# SW3S.net
KiCad netlist of a schematic drawn in EAGLE
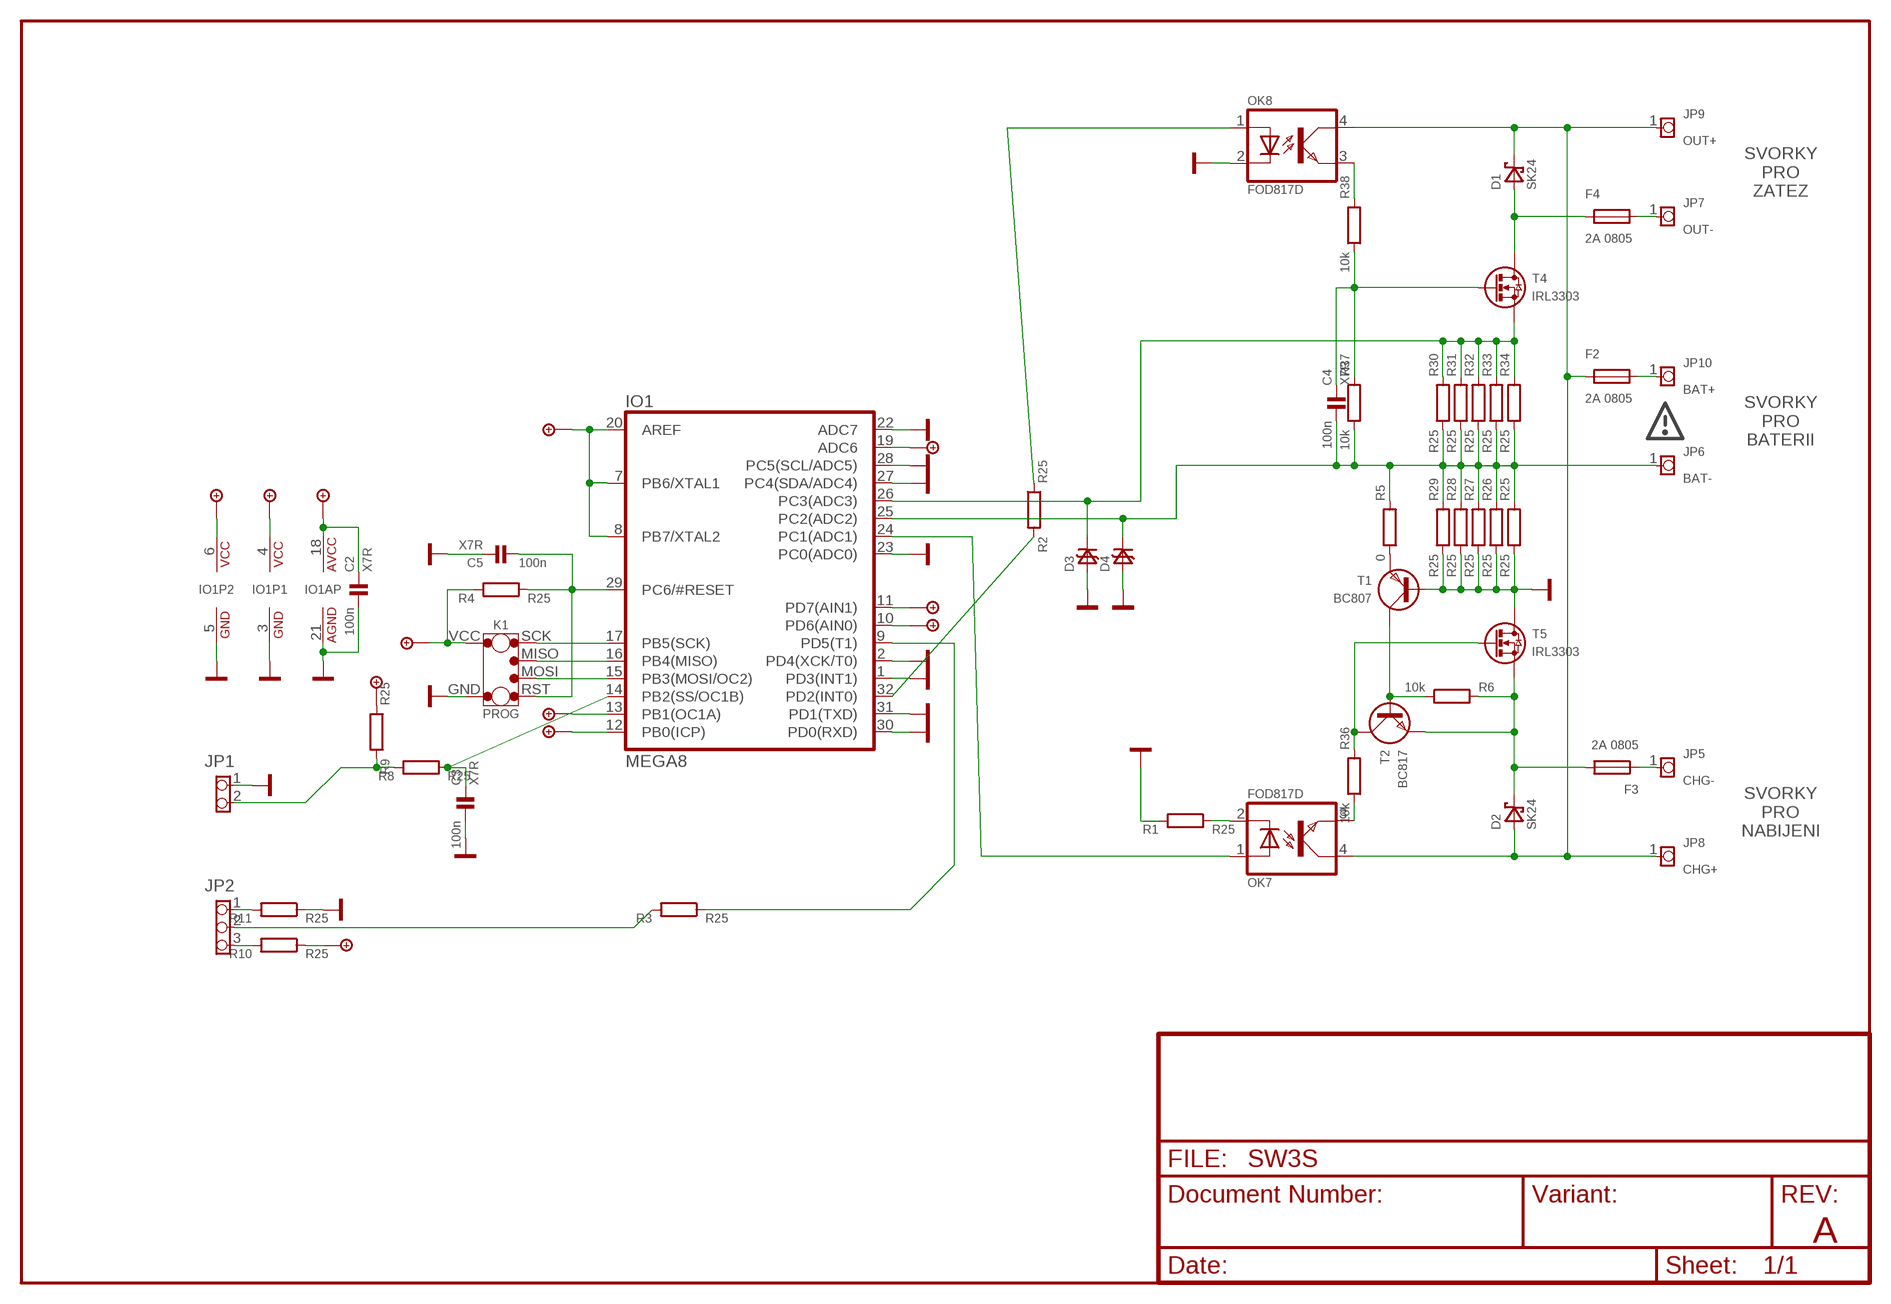
[diagram p0: schematic, sheet 1]

(export (version "E")
  (design (tool "Eeschema 10.0.6"))
  (components
    (comp (ref "C2")
      (value "100n")
      (footprint "eagle-import:0805")
      (libsource (lib "eagle-import") (part "C0805"))
    )
    (comp (ref "C3")
      (value "100n")
      (footprint "eagle-import:0805")
      (libsource (lib "eagle-import") (part "C0805"))
    )
    (comp (ref "C4")
      (value "100n")
      (footprint "eagle-import:0805")
      (libsource (lib "eagle-import") (part "C0805"))
    )
    (comp (ref "C5")
      (value "100n")
      (footprint "eagle-import:0805")
      (libsource (lib "eagle-import") (part "C0805"))
    )
    (comp (ref "D1")
      (value "SK24")
      (footprint "eagle-import:D_SMB")
      (libsource (lib "eagle-import") (part "D_SCHOTKY_SMB"))
    )
    (comp (ref "D2")
      (value "SK24")
      (footprint "eagle-import:D_SMB")
      (libsource (lib "eagle-import") (part "D_SCHOTKY_SMB"))
    )
    (comp (ref "D3")
      (value "D_TRANSIL_MLL34")
      (footprint "eagle-import:D_MLL34")
      (libsource (lib "eagle-import") (part "D_TRANSIL_MLL34"))
    )
    (comp (ref "D4")
      (value "D_TRANSIL_MLL34")
      (footprint "eagle-import:D_MLL34")
      (libsource (lib "eagle-import") (part "D_TRANSIL_MLL34"))
    )
    (comp (ref "F2")
      (value "2A 0805")
      (footprint "eagle-import:0805")
      (libsource (lib "eagle-import") (part "F_0805"))
    )
    (comp (ref "F3")
      (value "2A 0805")
      (footprint "eagle-import:0805")
      (libsource (lib "eagle-import") (part "F_0805"))
    )
    (comp (ref "F4")
      (value "2A 0805")
      (footprint "eagle-import:0805")
      (libsource (lib "eagle-import") (part "F_0805"))
    )
    (comp (ref "IO1")
      (value "MEGA8")
      (footprint "eagle-import:TQFP32")
      (libsource (lib "eagle-import") (part "MEGA8"))
    )
    (comp (ref "JP1")
      (value "PINHD-1X2_254_EDGE")
      (footprint "eagle-import:1X02_254_EDGE")
      (libsource (lib "eagle-import") (part "PINHD-1X2_254_EDGE"))
    )
    (comp (ref "JP2")
      (value "PINHD-1X3_254_EDGE")
      (footprint "eagle-import:1X03_254_EDGE")
      (libsource (lib "eagle-import") (part "PINHD-1X3_254_EDGE"))
    )
    (comp (ref "JP5")
      (value "CHG-")
      (footprint "eagle-import:1X01_254_PAD")
      (libsource (lib "eagle-import") (part "PINHD-1X1_254_PAD"))
    )
    (comp (ref "JP6")
      (value "BAT-")
      (footprint "eagle-import:1X01_254_PAD")
      (libsource (lib "eagle-import") (part "PINHD-1X1_254_PAD"))
    )
    (comp (ref "JP7")
      (value "OUT-")
      (footprint "eagle-import:1X01_254_PAD")
      (libsource (lib "eagle-import") (part "PINHD-1X1_254_PAD"))
    )
    (comp (ref "JP8")
      (value "CHG+")
      (footprint "eagle-import:1X01_254_PAD")
      (libsource (lib "eagle-import") (part "PINHD-1X1_254_PAD"))
    )
    (comp (ref "JP9")
      (value "OUT+")
      (footprint "eagle-import:1X01_254_PAD")
      (libsource (lib "eagle-import") (part "PINHD-1X1_254_PAD"))
    )
    (comp (ref "JP10")
      (value "BAT+")
      (footprint "eagle-import:1X01_254_PAD")
      (libsource (lib "eagle-import") (part "PINHD-1X1_254_PAD"))
    )
    (comp (ref "K1")
      (value "PROG")
      (footprint "eagle-import:PROG")
      (libsource (lib "eagle-import") (part "PROG"))
    )
    (comp (ref "OK7")
      (value "FOD817D")
      (footprint "eagle-import:SO04")
      (libsource (lib "eagle-import") (part "OC_T_NOBASE"))
    )
    (comp (ref "OK8")
      (value "FOD817D")
      (footprint "eagle-import:SO04")
      (libsource (lib "eagle-import") (part "OC_T_NOBASE"))
    )
    (comp (ref "R1")
      (value "R25")
      (footprint "eagle-import:0805")
      (libsource (lib "eagle-import") (part "R_R0805"))
    )
    (comp (ref "R2")
      (value "R25")
      (footprint "eagle-import:0805")
      (libsource (lib "eagle-import") (part "R_R0805"))
    )
    (comp (ref "R3")
      (value "R25")
      (footprint "eagle-import:0805")
      (libsource (lib "eagle-import") (part "R_R0805"))
    )
    (comp (ref "R4")
      (value "R25")
      (footprint "eagle-import:0805")
      (libsource (lib "eagle-import") (part "R_R0805"))
    )
    (comp (ref "R5")
      (value "0")
      (footprint "eagle-import:0805")
      (libsource (lib "eagle-import") (part "R_R0805"))
    )
    (comp (ref "R6")
      (value "10k")
      (footprint "eagle-import:0805")
      (libsource (lib "eagle-import") (part "R_R0805"))
    )
    (comp (ref "R8")
      (value "R25")
      (footprint "eagle-import:0805")
      (libsource (lib "eagle-import") (part "R_R0805"))
    )
    (comp (ref "R9")
      (value "R25")
      (footprint "eagle-import:0805")
      (libsource (lib "eagle-import") (part "R_R0805"))
    )
    (comp (ref "R10")
      (value "R25")
      (footprint "eagle-import:0805")
      (libsource (lib "eagle-import") (part "R_R0805"))
    )
    (comp (ref "R11")
      (value "R25")
      (footprint "eagle-import:0805")
      (libsource (lib "eagle-import") (part "R_R0805"))
    )
    (comp (ref "R25")
      (value "R25")
      (footprint "eagle-import:0805")
      (libsource (lib "eagle-import") (part "R_R0805"))
    )
    (comp (ref "R26")
      (value "R25")
      (footprint "eagle-import:0805")
      (libsource (lib "eagle-import") (part "R_R0805"))
    )
    (comp (ref "R27")
      (value "R25")
      (footprint "eagle-import:0805")
      (libsource (lib "eagle-import") (part "R_R0805"))
    )
    (comp (ref "R28")
      (value "R25")
      (footprint "eagle-import:0805")
      (libsource (lib "eagle-import") (part "R_R0805"))
    )
    (comp (ref "R29")
      (value "R25")
      (footprint "eagle-import:0805")
      (libsource (lib "eagle-import") (part "R_R0805"))
    )
    (comp (ref "R30")
      (value "R25")
      (footprint "eagle-import:0805")
      (libsource (lib "eagle-import") (part "R_R0805"))
    )
    (comp (ref "R31")
      (value "R25")
      (footprint "eagle-import:0805")
      (libsource (lib "eagle-import") (part "R_R0805"))
    )
    (comp (ref "R32")
      (value "R25")
      (footprint "eagle-import:0805")
      (libsource (lib "eagle-import") (part "R_R0805"))
    )
    (comp (ref "R33")
      (value "R25")
      (footprint "eagle-import:0805")
      (libsource (lib "eagle-import") (part "R_R0805"))
    )
    (comp (ref "R34")
      (value "R25")
      (footprint "eagle-import:0805")
      (libsource (lib "eagle-import") (part "R_R0805"))
    )
    (comp (ref "R36")
      (value "10k")
      (footprint "eagle-import:0805")
      (libsource (lib "eagle-import") (part "R_R0805"))
    )
    (comp (ref "R37")
      (value "10k")
      (footprint "eagle-import:0805")
      (libsource (lib "eagle-import") (part "R_R0805"))
    )
    (comp (ref "R38")
      (value "10k")
      (footprint "eagle-import:0805")
      (libsource (lib "eagle-import") (part "R_R0805"))
    )
    (comp (ref "T1")
      (value "BC807")
      (footprint "eagle-import:SOT23")
      (libsource (lib "eagle-import") (part "_PNP_SOT23_BCE"))
    )
    (comp (ref "T2")
      (value "BC817")
      (footprint "eagle-import:SOT23")
      (libsource (lib "eagle-import") (part "_NPN_SOT23_BCE"))
    )
    (comp (ref "T4")
      (value "IRL3303")
      (footprint "eagle-import:TO252")
      (libsource (lib "eagle-import") (part "_EMOS_N_TO252_GDS"))
    )
    (comp (ref "T5")
      (value "IRL3303")
      (footprint "eagle-import:TO252")
      (libsource (lib "eagle-import") (part "_EMOS_N_TO252_GDS"))
    )
  )
  (nets
    (net (code "1") (name "+5V") (class "Default")
      (node (ref "C2") (pin "1") (pinfunction "1_1") (pintype "passive"))
      (node (ref "IO1") (pin "10") (pinfunction "PD6(AIN0)_10") (pintype "passive"))
      (node (ref "IO1") (pin "11") (pinfunction "PD7(AIN1)_11") (pintype "passive"))
      (node (ref "IO1") (pin "12") (pinfunction "PB0(ICP)_12") (pintype "passive"))
      (node (ref "IO1") (pin "13") (pinfunction "PB1(OC1A)_13") (pintype "passive"))
      (node (ref "IO1") (pin "18") (pinfunction "VCC_18") (pintype "passive"))
      (node (ref "IO1") (pin "19") (pinfunction "ADC6_19") (pintype "passive"))
      (node (ref "IO1") (pin "20") (pinfunction "AREF_20") (pintype "passive"))
      (node (ref "IO1") (pin "4") (pinfunction "VCC_4") (pintype "passive"))
      (node (ref "IO1") (pin "6") (pinfunction "VCC_6") (pintype "passive"))
      (node (ref "IO1") (pin "7") (pinfunction "PB6/XTAL1_7") (pintype "passive"))
      (node (ref "IO1") (pin "8") (pinfunction "PB7/XTAL2_8") (pintype "passive"))
      (node (ref "K1") (pin "VCC") (pinfunction "VCC_VCC") (pintype "passive"))
      (node (ref "R10") (pin "1") (pinfunction "1_1") (pintype "passive"))
      (node (ref "R4") (pin "2") (pinfunction "2_2") (pintype "passive"))
      (node (ref "R9") (pin "1") (pinfunction "1_1") (pintype "passive"))
    )
    (net (code "2") (name "GND") (class "Default")
      (node (ref "C2") (pin "2") (pinfunction "2_2") (pintype "passive"))
      (node (ref "C3") (pin "2") (pinfunction "2_2") (pintype "passive"))
      (node (ref "C5") (pin "1") (pinfunction "1_1") (pintype "passive"))
      (node (ref "D3") (pin "A") (pinfunction "A_A") (pintype "passive"))
      (node (ref "D4") (pin "A") (pinfunction "A_A") (pintype "passive"))
      (node (ref "IO1") (pin "1") (pinfunction "PD3(INT1)_1") (pintype "passive"))
      (node (ref "IO1") (pin "2") (pinfunction "PD4(XCK/T0)_2") (pintype "passive"))
      (node (ref "IO1") (pin "21") (pinfunction "GND_21") (pintype "passive"))
      (node (ref "IO1") (pin "22") (pinfunction "ADC7_22") (pintype "passive"))
      (node (ref "IO1") (pin "23") (pinfunction "PC0(ADC0)_23") (pintype "passive"))
      (node (ref "IO1") (pin "27") (pinfunction "PC4(SDA/ADC4)_27") (pintype "passive"))
      (node (ref "IO1") (pin "28") (pinfunction "PC5(SCL/ADC5)_28") (pintype "passive"))
      (node (ref "IO1") (pin "3") (pinfunction "GND_3") (pintype "power_in"))
      (node (ref "IO1") (pin "30") (pinfunction "PD0(RXD)_30") (pintype "passive"))
      (node (ref "IO1") (pin "31") (pinfunction "PD1(TXD)_31") (pintype "passive"))
      (node (ref "IO1") (pin "5") (pinfunction "GND_5") (pintype "power_in"))
      (node (ref "JP1") (pin "1") (pinfunction "1_1") (pintype "passive"))
      (node (ref "K1") (pin "GND") (pinfunction "GND_GND") (pintype "passive"))
      (node (ref "OK8") (pin "2") (pinfunction "C_2") (pintype "passive"))
      (node (ref "R1") (pin "2") (pinfunction "2_2") (pintype "passive"))
      (node (ref "R11") (pin "1") (pinfunction "1_1") (pintype "passive"))
      (node (ref "R25") (pin "1") (pinfunction "1_1") (pintype "passive"))
      (node (ref "R26") (pin "1") (pinfunction "1_1") (pintype "passive"))
      (node (ref "R27") (pin "1") (pinfunction "1_1") (pintype "passive"))
      (node (ref "R28") (pin "1") (pinfunction "1_1") (pintype "passive"))
      (node (ref "R29") (pin "1") (pinfunction "1_1") (pintype "passive"))
      (node (ref "T1") (pin "1") (pinfunction "B_1") (pintype "passive"))
      (node (ref "T5") (pin "2") (pinfunction "D_2") (pintype "passive"))
    )
    (net (code "3") (name "Net-(F2-Pad2)") (class "Default")
      (node (ref "F2") (pin "2") (pinfunction "2_2") (pintype "passive"))
      (node (ref "JP10") (pin "1") (pinfunction "1_1") (pintype "passive"))
    )
    (net (code "4") (name "Net-(F3-Pad1)") (class "Default")
      (node (ref "F3") (pin "1") (pinfunction "1_1") (pintype "passive"))
      (node (ref "JP5") (pin "1") (pinfunction "1_1") (pintype "passive"))
    )
    (net (code "5") (name "Net-(F4-Pad2)") (class "Default")
      (node (ref "F4") (pin "2") (pinfunction "2_2") (pintype "passive"))
      (node (ref "JP7") (pin "1") (pinfunction "1_1") (pintype "passive"))
    )
    (net (code "6") (name "Net-(IO1A-PB2(SS{slash}OC1B))") (class "Default")
      (node (ref "C3") (pin "1") (pinfunction "1_1") (pintype "passive"))
      (node (ref "IO1") (pin "14") (pinfunction "PB2(SS/OC1B)_14") (pintype "passive"))
      (node (ref "R8") (pin "1") (pinfunction "1_1") (pintype "passive"))
    )
    (net (code "7") (name "Net-(IO1A-PB3(MOSI{slash}OC2))") (class "Default")
      (node (ref "IO1") (pin "15") (pinfunction "PB3(MOSI/OC2)_15") (pintype "passive"))
      (node (ref "K1") (pin "MOSI") (pinfunction "MOSI_MOSI") (pintype "passive"))
    )
    (net (code "8") (name "Net-(IO1A-PB4(MISO))") (class "Default")
      (node (ref "IO1") (pin "16") (pinfunction "PB4(MISO)_16") (pintype "passive"))
      (node (ref "K1") (pin "MISO") (pinfunction "MISO_MISO") (pintype "passive"))
    )
    (net (code "9") (name "Net-(IO1A-PB5(SCK))") (class "Default")
      (node (ref "IO1") (pin "17") (pinfunction "PB5(SCK)_17") (pintype "passive"))
      (node (ref "K1") (pin "SCK") (pinfunction "SCK_SCK") (pintype "passive"))
    )
    (net (code "10") (name "Net-(IO1A-PC1(ADC1))") (class "Default")
      (node (ref "IO1") (pin "24") (pinfunction "PC1(ADC1)_24") (pintype "passive"))
      (node (ref "OK7") (pin "1") (pinfunction "A_1") (pintype "passive"))
    )
    (net (code "11") (name "Net-(IO1A-PC2(ADC2))") (class "Default")
      (node (ref "C4") (pin "2") (pinfunction "2_2") (pintype "passive"))
      (node (ref "D4") (pin "K") (pinfunction "K_K") (pintype "passive"))
      (node (ref "IO1") (pin "25") (pinfunction "PC2(ADC2)_25") (pintype "passive"))
      (node (ref "JP6") (pin "1") (pinfunction "1_1") (pintype "passive"))
      (node (ref "R25") (pin "2") (pinfunction "2_2") (pintype "passive"))
      (node (ref "R26") (pin "2") (pinfunction "2_2") (pintype "passive"))
      (node (ref "R27") (pin "2") (pinfunction "2_2") (pintype "passive"))
      (node (ref "R28") (pin "2") (pinfunction "2_2") (pintype "passive"))
      (node (ref "R29") (pin "2") (pinfunction "2_2") (pintype "passive"))
      (node (ref "R30") (pin "1") (pinfunction "1_1") (pintype "passive"))
      (node (ref "R31") (pin "1") (pinfunction "1_1") (pintype "passive"))
      (node (ref "R32") (pin "1") (pinfunction "1_1") (pintype "passive"))
      (node (ref "R33") (pin "1") (pinfunction "1_1") (pintype "passive"))
      (node (ref "R34") (pin "1") (pinfunction "1_1") (pintype "passive"))
      (node (ref "R37") (pin "1") (pinfunction "1_1") (pintype "passive"))
      (node (ref "R5") (pin "2") (pinfunction "2_2") (pintype "passive"))
    )
    (net (code "12") (name "Net-(IO1A-PC3(ADC3))") (class "Default")
      (node (ref "D3") (pin "K") (pinfunction "K_K") (pintype "passive"))
      (node (ref "IO1") (pin "26") (pinfunction "PC3(ADC3)_26") (pintype "passive"))
      (node (ref "R30") (pin "2") (pinfunction "2_2") (pintype "passive"))
      (node (ref "R31") (pin "2") (pinfunction "2_2") (pintype "passive"))
      (node (ref "R32") (pin "2") (pinfunction "2_2") (pintype "passive"))
      (node (ref "R33") (pin "2") (pinfunction "2_2") (pintype "passive"))
      (node (ref "R34") (pin "2") (pinfunction "2_2") (pintype "passive"))
      (node (ref "T4") (pin "3") (pinfunction "S_3") (pintype "passive"))
    )
    (net (code "13") (name "Net-(IO1A-PC6{slash}#RESET)") (class "Default")
      (node (ref "C5") (pin "2") (pinfunction "2_2") (pintype "passive"))
      (node (ref "IO1") (pin "29") (pinfunction "PC6/#RESET_29") (pintype "passive"))
      (node (ref "K1") (pin "RST") (pinfunction "RST_RST") (pintype "passive"))
      (node (ref "R4") (pin "1") (pinfunction "1_1") (pintype "passive"))
    )
    (net (code "14") (name "Net-(IO1A-PD2(INT0))") (class "Default")
      (node (ref "IO1") (pin "32") (pinfunction "PD2(INT0)_32") (pintype "passive"))
      (node (ref "R2") (pin "2") (pinfunction "2_2") (pintype "passive"))
    )
    (net (code "15") (name "Net-(IO1A-PD5(T1))") (class "Default")
      (node (ref "IO1") (pin "9") (pinfunction "PD5(T1)_9") (pintype "passive"))
      (node (ref "R3") (pin "1") (pinfunction "1_1") (pintype "passive"))
    )
    (net (code "16") (name "Net-(JP1-Pad2)") (class "Default")
      (node (ref "JP1") (pin "2") (pinfunction "2_2") (pintype "passive"))
      (node (ref "R8") (pin "2") (pinfunction "2_2") (pintype "passive"))
      (node (ref "R9") (pin "2") (pinfunction "2_2") (pintype "passive"))
    )
    (net (code "17") (name "Net-(JP2-Pad1)") (class "Default")
      (node (ref "JP2") (pin "1") (pinfunction "1_1") (pintype "passive"))
      (node (ref "R11") (pin "2") (pinfunction "2_2") (pintype "passive"))
    )
    (net (code "18") (name "Net-(JP2-Pad2)") (class "Default")
      (node (ref "JP2") (pin "2") (pinfunction "2_2") (pintype "passive"))
      (node (ref "R3") (pin "2") (pinfunction "2_2") (pintype "passive"))
    )
    (net (code "19") (name "Net-(JP2-Pad3)") (class "Default")
      (node (ref "JP2") (pin "3") (pinfunction "3_3") (pintype "passive"))
      (node (ref "R10") (pin "2") (pinfunction "2_2") (pintype "passive"))
    )
    (net (code "20") (name "Net-(OK7-C)") (class "Default")
      (node (ref "OK7") (pin "2") (pinfunction "C_2") (pintype "passive"))
      (node (ref "R1") (pin "1") (pinfunction "1_1") (pintype "passive"))
    )
    (net (code "21") (name "Net-(OK7-COL)") (class "Default")
      (node (ref "D1") (pin "K") (pinfunction "K_K") (pintype "passive"))
      (node (ref "D2") (pin "A") (pinfunction "A_A") (pintype "passive"))
      (node (ref "F2") (pin "1") (pinfunction "1_1") (pintype "passive"))
      (node (ref "JP8") (pin "1") (pinfunction "1_1") (pintype "passive"))
      (node (ref "JP9") (pin "1") (pinfunction "1_1") (pintype "passive"))
      (node (ref "OK7") (pin "4") (pinfunction "COL_4") (pintype "passive"))
      (node (ref "OK8") (pin "4") (pinfunction "COL_4") (pintype "passive"))
    )
    (net (code "22") (name "Net-(OK7-EMIT)") (class "Default")
      (node (ref "OK7") (pin "3") (pinfunction "EMIT_3") (pintype "passive"))
      (node (ref "R36") (pin "1") (pinfunction "1_1") (pintype "passive"))
    )
    (net (code "23") (name "Net-(OK8-A)") (class "Default")
      (node (ref "OK8") (pin "1") (pinfunction "A_1") (pintype "passive"))
      (node (ref "R2") (pin "1") (pinfunction "1_1") (pintype "passive"))
    )
    (net (code "24") (name "Net-(OK8-EMIT)") (class "Default")
      (node (ref "OK8") (pin "3") (pinfunction "EMIT_3") (pintype "passive"))
      (node (ref "R38") (pin "2") (pinfunction "2_2") (pintype "passive"))
    )
    (net (code "25") (name "Net-(T1-C)") (class "Default")
      (node (ref "R6") (pin "1") (pinfunction "1_1") (pintype "passive"))
      (node (ref "T1") (pin "2") (pinfunction "C_2") (pintype "passive"))
      (node (ref "T2") (pin "1") (pinfunction "B_1") (pintype "passive"))
    )
    (net (code "26") (name "Net-(T1-E)") (class "Default")
      (node (ref "R5") (pin "1") (pinfunction "1_1") (pintype "passive"))
      (node (ref "T1") (pin "3") (pinfunction "E_3") (pintype "passive"))
    )
    (net (code "27") (name "Net-(T2-C)") (class "Default")
      (node (ref "R36") (pin "2") (pinfunction "2_2") (pintype "passive"))
      (node (ref "T2") (pin "2") (pinfunction "C_2") (pintype "passive"))
      (node (ref "T5") (pin "1") (pinfunction "G_1") (pintype "passive"))
    )
    (net (code "28") (name "Net-(T2-E)") (class "Default")
      (node (ref "D2") (pin "K") (pinfunction "K_K") (pintype "passive"))
      (node (ref "F3") (pin "2") (pinfunction "2_2") (pintype "passive"))
      (node (ref "R6") (pin "2") (pinfunction "2_2") (pintype "passive"))
      (node (ref "T2") (pin "3") (pinfunction "E_3") (pintype "passive"))
      (node (ref "T5") (pin "3") (pinfunction "S_3") (pintype "passive"))
    )
    (net (code "29") (name "Net-(T4-D)") (class "Default")
      (node (ref "D1") (pin "A") (pinfunction "A_A") (pintype "passive"))
      (node (ref "F4") (pin "1") (pinfunction "1_1") (pintype "passive"))
      (node (ref "T4") (pin "2") (pinfunction "D_2") (pintype "passive"))
    )
    (net (code "30") (name "Net-(T4-G)") (class "Default")
      (node (ref "C4") (pin "1") (pinfunction "1_1") (pintype "passive"))
      (node (ref "R37") (pin "2") (pinfunction "2_2") (pintype "passive"))
      (node (ref "R38") (pin "1") (pinfunction "1_1") (pintype "passive"))
      (node (ref "T4") (pin "1") (pinfunction "G_1") (pintype "passive"))
    )
  )
)
